# slaveboard.net
KiCad netlist of a schematic drawn in EAGLE
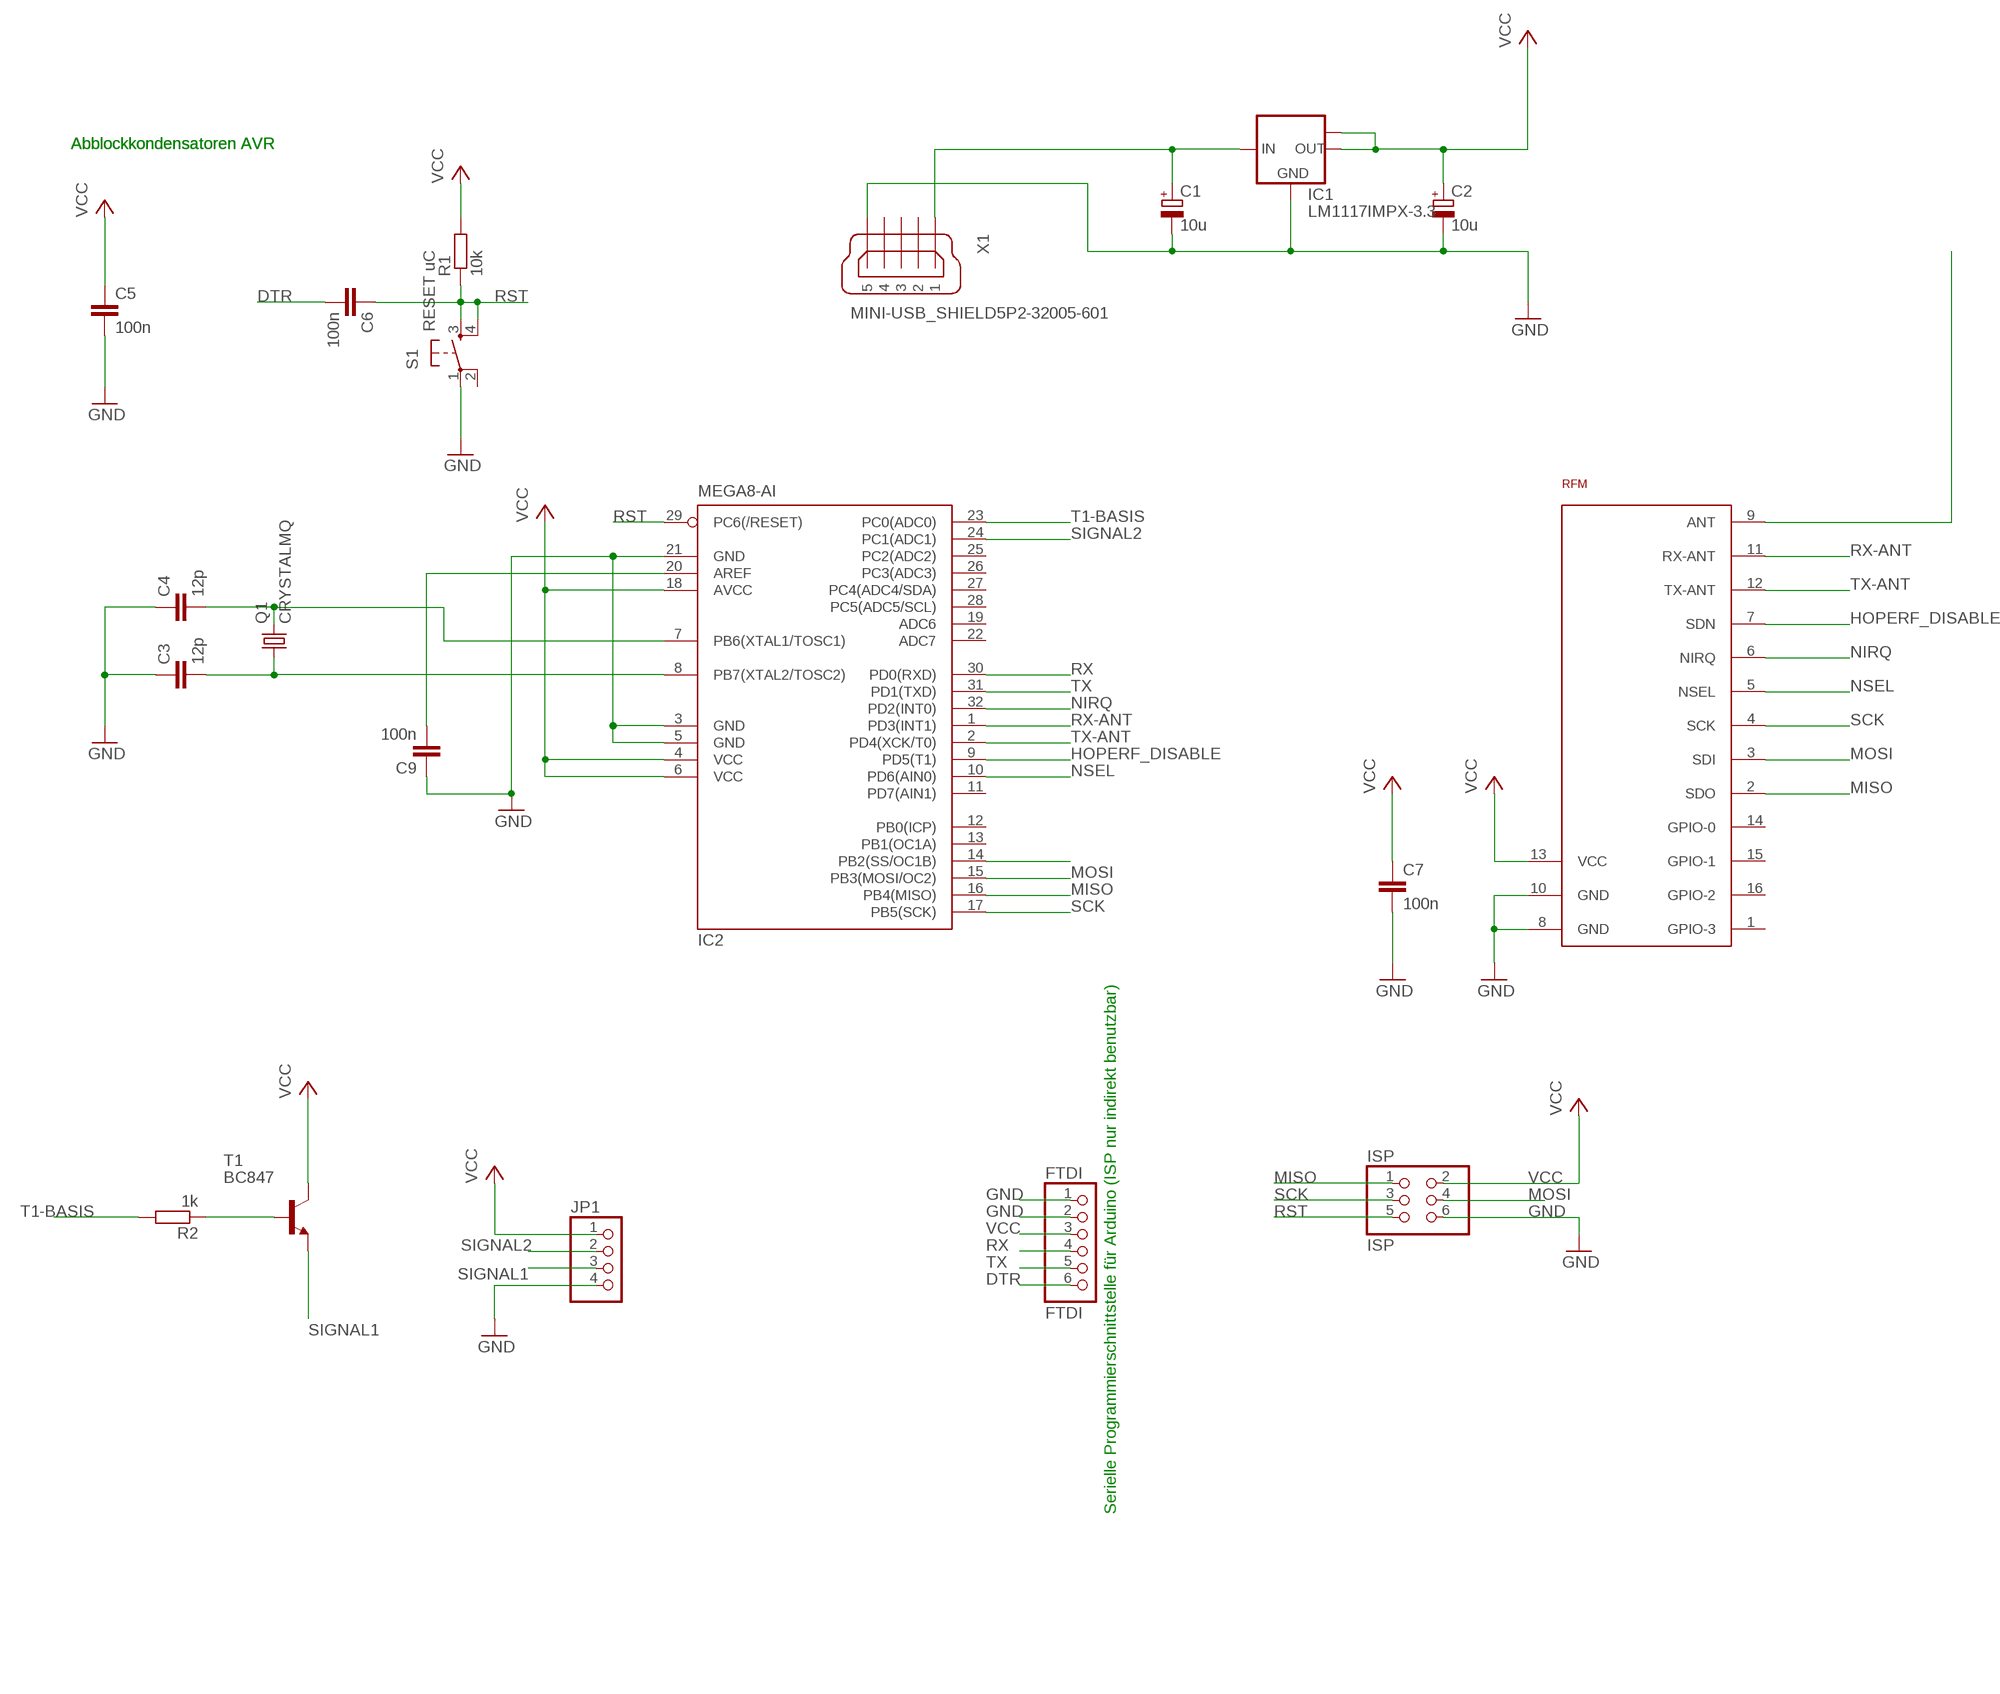
[diagram p0: schematic, sheet 1]

(export (version "E")
  (design (tool "Eeschema 10.0.6"))
  (components
    (comp (ref "C1")
      (value "10u")
      (footprint "eagle-import:CT6032")
      (libsource (lib "eagle-import") (part "CPOL-EUCT6032"))
    )
    (comp (ref "C2")
      (value "10u")
      (footprint "eagle-import:CT6032")
      (libsource (lib "eagle-import") (part "CPOL-EUCT6032"))
    )
    (comp (ref "C3")
      (value "12p")
      (footprint "eagle-import:C0603")
      (libsource (lib "eagle-import") (part "C-EUC0603"))
    )
    (comp (ref "C4")
      (value "12p")
      (footprint "eagle-import:C0603")
      (libsource (lib "eagle-import") (part "C-EUC0603"))
    )
    (comp (ref "C5")
      (value "100n")
      (footprint "eagle-import:C0603")
      (libsource (lib "eagle-import") (part "C-EUC0603"))
    )
    (comp (ref "C6")
      (value "100n")
      (footprint "eagle-import:C0603")
      (libsource (lib "eagle-import") (part "C-EUC0603"))
    )
    (comp (ref "C7")
      (value "100n")
      (footprint "eagle-import:C0603")
      (libsource (lib "eagle-import") (part "C-EUC0603"))
    )
    (comp (ref "C9")
      (value "100n")
      (footprint "eagle-import:C0603")
      (libsource (lib "eagle-import") (part "C-EUC0603"))
    )
    (comp (ref "FTDI")
      (value "FTDI")
      (footprint "eagle-import:1X06_90")
      (libsource (lib "eagle-import") (part "PINHD-1X6/90"))
    )
    (comp (ref "IC1")
      (value "LM1117IMPX-3.3")
      (footprint "eagle-import:SOT223")
      (libsource (lib "eagle-import") (part "LM1117IMPX-3.3"))
    )
    (comp (ref "IC2")
      (value "MEGA8-AI")
      (footprint "eagle-import:TQFP32-08")
      (fields (field (name "MPN") "ATMEGA8-16AU"))
      (libsource (lib "eagle-import") (part "MEGA8-AI"))
    )
    (comp (ref "ISP")
      (value "ISP")
      (footprint "eagle-import:2X03")
      (libsource (lib "eagle-import") (part "PINHD-2X3"))
    )
    (comp (ref "JP1")
      (value "PINHD-1X4/90")
      (footprint "eagle-import:1X04_90")
      (libsource (lib "eagle-import") (part "PINHD-1X4/90"))
    )
    (comp (ref "Q1")
      (value "CRYSTALMQ")
      (footprint "eagle-import:MQ")
      (libsource (lib "eagle-import") (part "CRYSTALMQ"))
    )
    (comp (ref "R1")
      (value "10k")
      (footprint "eagle-import:R0805")
      (libsource (lib "eagle-import") (part "R-EU_R0805"))
    )
    (comp (ref "R2")
      (value "1k")
      (footprint "eagle-import:R0805")
      (libsource (lib "eagle-import") (part "R-EU_R0805"))
    )
    (comp (ref "RFM")
      (value "HOPERF-DB")
      (footprint "eagle-import:HOPERF-DB")
      (libsource (lib "eagle-import") (part "HOPERF-DB"))
    )
    (comp (ref "S1")
      (value "RESET uC")
      (footprint "eagle-import:RAFI")
      (libsource (lib "eagle-import") (part "10-XXB3FRAFI"))
    )
    (comp (ref "T1")
      (value "BC847")
      (footprint "eagle-import:SOT23")
      (libsource (lib "eagle-import") (part "BC847"))
    )
    (comp (ref "X1")
      (value "MINI-USB_SHIELD5P2-32005-601")
      (footprint "eagle-import:32005-601")
      (libsource (lib "eagle-import") (part "MINI-USB_SHIELD5P2-32005-601"))
    )
  )
  (nets
    (net (code "1") (name "/DTR") (class "Default")
      (node (ref "C6") (pin "2") (pinfunction "2_2") (pintype "passive"))
      (node (ref "FTDI") (pin "6") (pinfunction "6_6") (pintype "passive"))
    )
    (net (code "2") (name "/HOPERF_DISABLE") (class "Default")
      (node (ref "IC2") (pin "9") (pinfunction "PD5(T1)_9") (pintype "bidirectional"))
      (node (ref "RFM") (pin "7") (pinfunction "SDN_7") (pintype "bidirectional"))
    )
    (net (code "3") (name "/MISO") (class "Default")
      (node (ref "IC2") (pin "16") (pinfunction "PB4(MISO)_16") (pintype "bidirectional"))
      (node (ref "ISP") (pin "1") (pinfunction "1_1") (pintype "passive"))
      (node (ref "RFM") (pin "2") (pinfunction "SDO_2") (pintype "bidirectional"))
    )
    (net (code "4") (name "/MOSI") (class "Default")
      (node (ref "IC2") (pin "15") (pinfunction "PB3(MOSI/OC2)_15") (pintype "bidirectional"))
      (node (ref "ISP") (pin "4") (pinfunction "4_4") (pintype "passive"))
      (node (ref "RFM") (pin "3") (pinfunction "SDI_3") (pintype "bidirectional"))
    )
    (net (code "5") (name "/NIRQ") (class "Default")
      (node (ref "IC2") (pin "32") (pinfunction "PD2(INT0)_32") (pintype "bidirectional"))
      (node (ref "RFM") (pin "6") (pinfunction "NIRQ_6") (pintype "bidirectional"))
    )
    (net (code "6") (name "/NSEL") (class "Default")
      (node (ref "IC2") (pin "10") (pinfunction "PD6(AIN0)_10") (pintype "bidirectional"))
      (node (ref "RFM") (pin "5") (pinfunction "NSEL_5") (pintype "bidirectional"))
    )
    (net (code "7") (name "/RST") (class "Default")
      (node (ref "C6") (pin "1") (pinfunction "1_1") (pintype "passive"))
      (node (ref "IC2") (pin "29") (pinfunction "PC6(/RESET)_29") (pintype "bidirectional"))
      (node (ref "ISP") (pin "5") (pinfunction "5_5") (pintype "passive"))
      (node (ref "R1") (pin "1") (pinfunction "1_1") (pintype "passive"))
      (node (ref "S1") (pin "3") (pinfunction "S_3") (pintype "passive"))
      (node (ref "S1") (pin "4") (pinfunction "S1_4") (pintype "passive"))
    )
    (net (code "8") (name "/RX") (class "Default")
      (node (ref "FTDI") (pin "4") (pinfunction "4_4") (pintype "passive"))
      (node (ref "IC2") (pin "30") (pinfunction "PD0(RXD)_30") (pintype "bidirectional"))
    )
    (net (code "9") (name "/RX-ANT") (class "Default")
      (node (ref "IC2") (pin "1") (pinfunction "PD3(INT1)_1") (pintype "bidirectional"))
      (node (ref "RFM") (pin "11") (pinfunction "RX-ANT_11") (pintype "bidirectional"))
    )
    (net (code "10") (name "/SCK") (class "Default")
      (node (ref "IC2") (pin "17") (pinfunction "PB5(SCK)_17") (pintype "bidirectional"))
      (node (ref "ISP") (pin "3") (pinfunction "3_3") (pintype "passive"))
      (node (ref "RFM") (pin "4") (pinfunction "SCK_4") (pintype "bidirectional"))
    )
    (net (code "11") (name "/SIGNAL1") (class "Default")
      (node (ref "JP1") (pin "3") (pinfunction "3_3") (pintype "passive"))
      (node (ref "T1") (pin "2") (pinfunction "E_2") (pintype "passive"))
    )
    (net (code "12") (name "/SIGNAL2") (class "Default")
      (node (ref "IC2") (pin "24") (pinfunction "PC1(ADC1)_24") (pintype "bidirectional"))
      (node (ref "JP1") (pin "2") (pinfunction "2_2") (pintype "passive"))
    )
    (net (code "13") (name "/T1-BASIS") (class "Default")
      (node (ref "IC2") (pin "23") (pinfunction "PC0(ADC0)_23") (pintype "bidirectional"))
      (node (ref "R2") (pin "2") (pinfunction "2_2") (pintype "passive"))
    )
    (net (code "14") (name "/TX") (class "Default")
      (node (ref "FTDI") (pin "5") (pinfunction "5_5") (pintype "passive"))
      (node (ref "IC2") (pin "31") (pinfunction "PD1(TXD)_31") (pintype "bidirectional"))
    )
    (net (code "15") (name "/TX-ANT") (class "Default")
      (node (ref "IC2") (pin "2") (pinfunction "PD4(XCK/T0)_2") (pintype "bidirectional"))
      (node (ref "RFM") (pin "12") (pinfunction "TX-ANT_12") (pintype "bidirectional"))
    )
    (net (code "16") (name "GND") (class "Default")
      (node (ref "C1") (pin "-") (pinfunction "-_-") (pintype "passive"))
      (node (ref "C2") (pin "-") (pinfunction "-_-") (pintype "passive"))
      (node (ref "C3") (pin "1") (pinfunction "1_1") (pintype "passive"))
      (node (ref "C4") (pin "1") (pinfunction "1_1") (pintype "passive"))
      (node (ref "C5") (pin "2") (pinfunction "2_2") (pintype "passive"))
      (node (ref "C7") (pin "2") (pinfunction "2_2") (pintype "passive"))
      (node (ref "C9") (pin "1") (pinfunction "1_1") (pintype "passive"))
      (node (ref "FTDI") (pin "1") (pinfunction "1_1") (pintype "passive"))
      (node (ref "FTDI") (pin "2") (pinfunction "2_2") (pintype "passive"))
      (node (ref "IC1") (pin "1") (pinfunction "GND_1") (pintype "input"))
      (node (ref "IC2") (pin "21") (pinfunction "GND_21") (pintype "power_in"))
      (node (ref "IC2") (pin "3") (pinfunction "GND_3") (pintype "power_in"))
      (node (ref "IC2") (pin "5") (pinfunction "GND_5") (pintype "power_in"))
      (node (ref "ISP") (pin "6") (pinfunction "6_6") (pintype "passive"))
      (node (ref "JP1") (pin "4") (pinfunction "4_4") (pintype "passive"))
      (node (ref "RFM") (pin "10") (pinfunction "GND_10") (pintype "bidirectional"))
      (node (ref "RFM") (pin "8") (pinfunction "GND_8") (pintype "bidirectional"))
      (node (ref "S1") (pin "1") (pinfunction "P_1") (pintype "passive"))
      (node (ref "X1") (pin "5") (pinfunction "5_5") (pintype "passive"))
    )
    (net (code "17") (name "Net-(IC1-IN)") (class "Default")
      (node (ref "C1") (pin "+") (pinfunction "+_+") (pintype "passive"))
      (node (ref "IC1") (pin "3") (pinfunction "IN_3") (pintype "input"))
      (node (ref "X1") (pin "1") (pinfunction "1_1") (pintype "passive"))
    )
    (net (code "18") (name "Net-(IC2-AREF)") (class "Default")
      (node (ref "C9") (pin "2") (pinfunction "2_2") (pintype "passive"))
      (node (ref "IC2") (pin "20") (pinfunction "AREF_20") (pintype "passive"))
    )
    (net (code "19") (name "Net-(IC2-PB6(XTAL1{slash}TOSC1))") (class "Default")
      (node (ref "C4") (pin "2") (pinfunction "2_2") (pintype "passive"))
      (node (ref "IC2") (pin "7") (pinfunction "PB6(XTAL1/TOSC1)_7") (pintype "bidirectional"))
      (node (ref "Q1") (pin "P3") (pinfunction "2_P3") (pintype "passive"))
    )
    (net (code "20") (name "Net-(IC2-PB7(XTAL2{slash}TOSC2))") (class "Default")
      (node (ref "C3") (pin "2") (pinfunction "2_2") (pintype "passive"))
      (node (ref "IC2") (pin "8") (pinfunction "PB7(XTAL2/TOSC2)_8") (pintype "bidirectional"))
      (node (ref "Q1") (pin "P1") (pinfunction "1_P1") (pintype "passive"))
    )
    (net (code "21") (name "Net-(T1-B)") (class "Default")
      (node (ref "R2") (pin "1") (pinfunction "1_1") (pintype "passive"))
      (node (ref "T1") (pin "1") (pinfunction "B_1") (pintype "passive"))
    )
    (net (code "22") (name "VCC") (class "Default")
      (node (ref "C2") (pin "+") (pinfunction "+_+") (pintype "passive"))
      (node (ref "C5") (pin "1") (pinfunction "1_1") (pintype "passive"))
      (node (ref "C7") (pin "1") (pinfunction "1_1") (pintype "passive"))
      (node (ref "FTDI") (pin "3") (pinfunction "3_3") (pintype "passive"))
      (node (ref "IC1") (pin "2") (pinfunction "OUT_2") (pintype "passive"))
      (node (ref "IC1") (pin "TAB") (pinfunction "OUT1_TAB") (pintype "passive"))
      (node (ref "IC2") (pin "18") (pinfunction "AVCC_18") (pintype "power_in"))
      (node (ref "IC2") (pin "4") (pinfunction "VCC_4") (pintype "power_in"))
      (node (ref "IC2") (pin "6") (pinfunction "VCC_6") (pintype "power_in"))
      (node (ref "ISP") (pin "2") (pinfunction "2_2") (pintype "passive"))
      (node (ref "JP1") (pin "1") (pinfunction "1_1") (pintype "passive"))
      (node (ref "R1") (pin "2") (pinfunction "2_2") (pintype "passive"))
      (node (ref "RFM") (pin "13") (pinfunction "VCC_13") (pintype "bidirectional"))
      (node (ref "T1") (pin "3") (pinfunction "C_3") (pintype "passive"))
    )
    (net (code "23") (name "unconnected-(IC2-ADC6-Pad19)") (class "Default")
      (node (ref "IC2") (pin "19") (pinfunction "ADC6_19") (pintype "bidirectional"))
    )
    (net (code "24") (name "unconnected-(IC2-ADC7-Pad22)") (class "Default")
      (node (ref "IC2") (pin "22") (pinfunction "ADC7_22") (pintype "bidirectional"))
    )
    (net (code "25") (name "unconnected-(IC2-PB0(ICP)-Pad12)") (class "Default")
      (node (ref "IC2") (pin "12") (pinfunction "PB0(ICP)_12") (pintype "bidirectional"))
    )
    (net (code "26") (name "unconnected-(IC2-PB1(OC1A)-Pad13)") (class "Default")
      (node (ref "IC2") (pin "13") (pinfunction "PB1(OC1A)_13") (pintype "bidirectional"))
    )
    (net (code "27") (name "unconnected-(IC2-PB2(SS{slash}OC1B)-Pad14)") (class "Default")
      (node (ref "IC2") (pin "14") (pinfunction "PB2(SS/OC1B)_14") (pintype "bidirectional"))
    )
    (net (code "28") (name "unconnected-(IC2-PC2(ADC2)-Pad25)") (class "Default")
      (node (ref "IC2") (pin "25") (pinfunction "PC2(ADC2)_25") (pintype "bidirectional"))
    )
    (net (code "29") (name "unconnected-(IC2-PC3(ADC3)-Pad26)") (class "Default")
      (node (ref "IC2") (pin "26") (pinfunction "PC3(ADC3)_26") (pintype "bidirectional"))
    )
    (net (code "30") (name "unconnected-(IC2-PC4(ADC4{slash}SDA)-Pad27)") (class "Default")
      (node (ref "IC2") (pin "27") (pinfunction "PC4(ADC4/SDA)_27") (pintype "bidirectional"))
    )
    (net (code "31") (name "unconnected-(IC2-PC5(ADC5{slash}SCL)-Pad28)") (class "Default")
      (node (ref "IC2") (pin "28") (pinfunction "PC5(ADC5/SCL)_28") (pintype "bidirectional"))
    )
    (net (code "32") (name "unconnected-(IC2-PD7(AIN1)-Pad11)") (class "Default")
      (node (ref "IC2") (pin "11") (pinfunction "PD7(AIN1)_11") (pintype "bidirectional"))
    )
    (net (code "33") (name "unconnected-(RFM-ANT-Pad9)") (class "Default")
      (node (ref "RFM") (pin "9") (pinfunction "ANT_9") (pintype "bidirectional"))
    )
    (net (code "34") (name "unconnected-(RFM-GPIO-0-Pad14)") (class "Default")
      (node (ref "RFM") (pin "14") (pinfunction "GPIO-0_14") (pintype "bidirectional"))
    )
    (net (code "35") (name "unconnected-(RFM-GPIO-1-Pad15)") (class "Default")
      (node (ref "RFM") (pin "15") (pinfunction "GPIO-1_15") (pintype "bidirectional"))
    )
    (net (code "36") (name "unconnected-(RFM-GPIO-2-Pad16)") (class "Default")
      (node (ref "RFM") (pin "16") (pinfunction "GPIO-2_16") (pintype "bidirectional"))
    )
    (net (code "37") (name "unconnected-(RFM-GPIO-3-Pad1)") (class "Default")
      (node (ref "RFM") (pin "1") (pinfunction "GPIO-3_1") (pintype "bidirectional"))
    )
    (net (code "38") (name "unconnected-(S1-P1-Pad2)") (class "Default")
      (node (ref "S1") (pin "2") (pinfunction "P1_2") (pintype "passive"))
    )
    (net (code "39") (name "unconnected-(X1-Pad2)") (class "Default")
      (node (ref "X1") (pin "2") (pinfunction "2_2") (pintype "passive"))
    )
    (net (code "40") (name "unconnected-(X1-Pad3)") (class "Default")
      (node (ref "X1") (pin "3") (pinfunction "3_3") (pintype "passive"))
    )
    (net (code "41") (name "unconnected-(X1-Pad4)") (class "Default")
      (node (ref "X1") (pin "4") (pinfunction "4_4") (pintype "passive"))
    )
  )
)
